# Output_curcuits_Page_3.net
KiCad netlist of a schematic drawn in Altium Designer
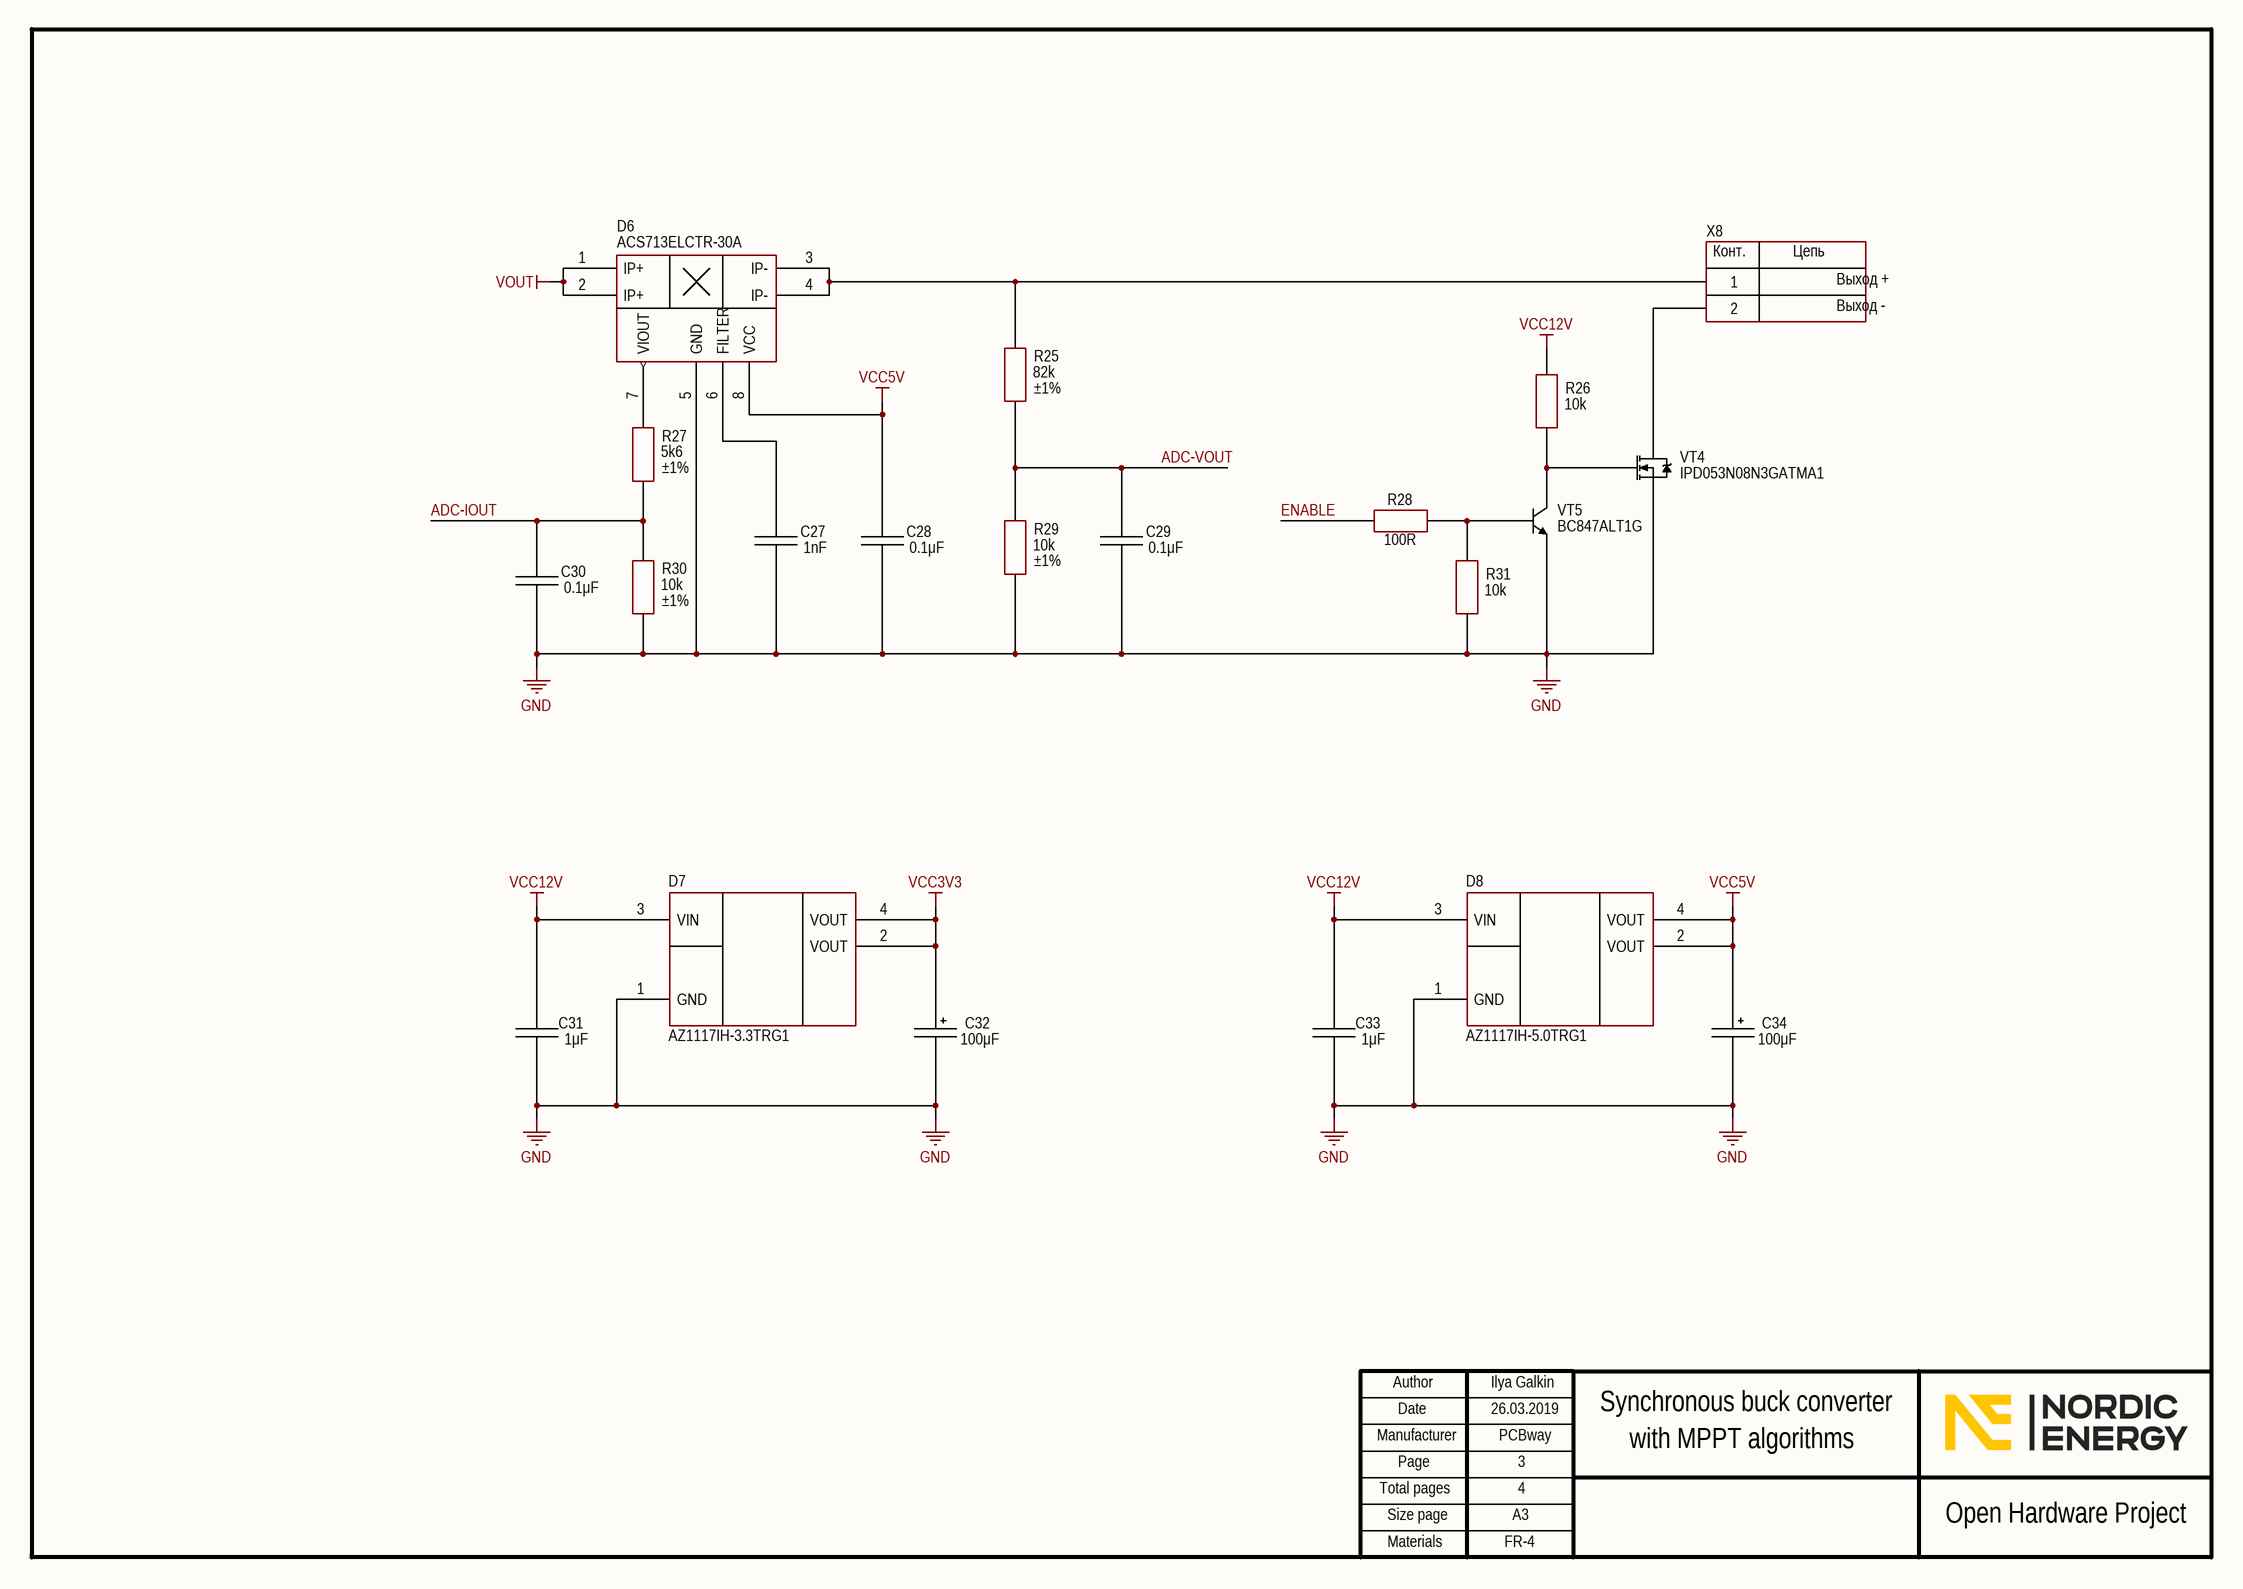
[diagram p0: Output curcuits. Page 3.SchDoc]

(export (version "E")
  (design (tool "Eeschema 10.0.6"))
  (components
    (comp (ref "C27")
      (value "1nF")
      (footprint "CH0805C")
      (fields (field (name "MANUFACTURER") "Yageo"))
      (libsource (lib "Discrete") (part "Capacitor"))
    )
    (comp (ref "C28")
      (value "0.1μF")
      (footprint "CH0805C")
      (fields (field (name "MANUFACTURER") "Yageo"))
      (libsource (lib "Discrete") (part "Capacitor"))
    )
    (comp (ref "C29")
      (value "0.1μF")
      (footprint "CH0805C")
      (fields (field (name "MANUFACTURER") "Yageo"))
      (libsource (lib "Discrete") (part "Capacitor"))
    )
    (comp (ref "C30")
      (value "0.1μF")
      (footprint "CH0805C")
      (fields (field (name "MANUFACTURER") "Yageo"))
      (libsource (lib "Discrete") (part "Capacitor"))
    )
    (comp (ref "C31")
      (value "1μF")
      (footprint "CH0805C")
      (fields (field (name "MANUFACTURER") "Yageo"))
      (libsource (lib "Discrete") (part "Capacitor"))
    )
    (comp (ref "C32")
      (value "100μF")
      (footprint "TANTAL_A")
      (fields (field (name "MANUFACTURER") "AVX"))
      (libsource (lib "Discrete") (part "TantalCap"))
    )
    (comp (ref "C33")
      (value "1μF")
      (footprint "CH0805C")
      (fields (field (name "MANUFACTURER") "Yageo"))
      (libsource (lib "Discrete") (part "Capacitor"))
    )
    (comp (ref "C34")
      (value "100μF")
      (footprint "TANTAL_A")
      (fields (field (name "MANUFACTURER") "AVX"))
      (libsource (lib "Discrete") (part "TantalCap"))
    )
    (comp (ref "D6")
      (value "ACS713ELCTR-30A")
      (footprint "8-SOIC")
      (description "Sensor")
      (fields (field (name "MANUFACTURER") "Allegro MicroSystems, LLC"))
      (libsource (lib "Power Supplies") (part "ACS713ELCTR-30A-T"))
    )
    (comp (ref "D7")
      (value "AZ1117IH-3.3TRG1")
      (footprint "SOT223")
      (description "LDO")
      (fields (field (name "MANUFACTURER") "Diodes Incorporated"))
      (libsource (lib "Power Supplies") (part "LDL1117S33R"))
    )
    (comp (ref "D8")
      (value "AZ1117IH-5.0TRG1")
      (footprint "SOT223")
      (description "LDO")
      (fields (field (name "MANUFACTURER") "Diodes Incorporated"))
      (libsource (lib "Power Supplies") (part "LDL1117S33R"))
    )
    (comp (ref "R25")
      (value "82k")
      (footprint "CH0805R")
      (fields (field (name "MANUFACTURER") "Yageo") (field (name "COMPONENTKIND") "±1%"))
      (libsource (lib "Discrete") (part "Resistor"))
    )
    (comp (ref "R26")
      (value "10k")
      (footprint "CH0805R")
      (fields (field (name "MANUFACTURER") "Yageo"))
      (libsource (lib "Discrete") (part "Resistor"))
    )
    (comp (ref "R27")
      (value "5k6")
      (footprint "CH0805R")
      (fields (field (name "MANUFACTURER") "Yageo") (field (name "COMPONENTKIND") "±1%"))
      (libsource (lib "Discrete") (part "Resistor"))
    )
    (comp (ref "R28")
      (value "100R")
      (footprint "CH0805R")
      (fields (field (name "MANUFACTURER") "Yageo"))
      (libsource (lib "") (part "Resistor_1"))
    )
    (comp (ref "R29")
      (value "10k")
      (footprint "CH0805R")
      (fields (field (name "MANUFACTURER") "Yageo") (field (name "COMPONENTKIND") "±1%"))
      (libsource (lib "Discrete") (part "Resistor"))
    )
    (comp (ref "R30")
      (value "10k")
      (footprint "CH0805R")
      (fields (field (name "MANUFACTURER") "Yageo") (field (name "COMPONENTKIND") "±1%"))
      (libsource (lib "Discrete") (part "Resistor"))
    )
    (comp (ref "R31")
      (value "10k")
      (footprint "CH0805R")
      (fields (field (name "MANUFACTURER") "Yageo"))
      (libsource (lib "Discrete") (part "Resistor"))
    )
    (comp (ref "VT4")
      (value "IPD053N08N3GATMA1")
      (footprint "D2PAK")
      (description "Mosfet")
      (fields (field (name "MANUFACTURER") "Infineon"))
      (libsource (lib "Transistor") (part "N-chanel"))
    )
    (comp (ref "VT5")
      (value "BC847ALT1G")
      (footprint "SOT23_123")
      (description "Bipolar")
      (fields (field (name "MANUFACTURER") "ON Semiconductor"))
      (libsource (lib "Transistor") (part "NPN"))
    )
    (comp (ref "X8")
      (value "6PCV-02-006")
      (footprint "CON: 6PCV-02-006")
      (fields (field (name "MANUFACTURER") "TE Connectivity"))
      (libsource (lib "Connectors") (part "2-Connector"))
    )
  )
  (nets
    (net (code "1") (name "/ADC-IOUT") (class "Default")
      (node (ref "C30") (pin "2") (pinfunction "2_2") (pintype "power_in"))
      (node (ref "R27") (pin "1") (pinfunction "1_1") (pintype "passive"))
      (node (ref "R30") (pin "2") (pinfunction "2_2") (pintype "passive"))
    )
    (net (code "2") (name "/ADC-VOUT") (class "Default")
      (node (ref "C29") (pin "2") (pinfunction "2_2") (pintype "power_in"))
      (node (ref "R25") (pin "1") (pinfunction "1_1") (pintype "passive"))
      (node (ref "R29") (pin "2") (pinfunction "2_2") (pintype "passive"))
    )
    (net (code "3") (name "/ENABLE") (class "Default")
      (node (ref "R28") (pin "1") (pinfunction "1_1") (pintype "passive"))
    )
    (net (code "4") (name "GND") (class "Default")
      (node (ref "C27") (pin "1") (pinfunction "1_1") (pintype "power_in"))
      (node (ref "C28") (pin "1") (pinfunction "1_1") (pintype "power_in"))
      (node (ref "C29") (pin "1") (pinfunction "1_1") (pintype "power_in"))
      (node (ref "C30") (pin "1") (pinfunction "1_1") (pintype "power_in"))
      (node (ref "C31") (pin "1") (pinfunction "1_1") (pintype "power_in"))
      (node (ref "C32") (pin "2") (pinfunction "2_2") (pintype "power_in"))
      (node (ref "C33") (pin "1") (pinfunction "1_1") (pintype "power_in"))
      (node (ref "C34") (pin "2") (pinfunction "2_2") (pintype "power_in"))
      (node (ref "D6") (pin "5") (pinfunction "GND_5") (pintype "passive"))
      (node (ref "D7") (pin "1") (pinfunction "GND_1") (pintype "power_in"))
      (node (ref "D8") (pin "1") (pinfunction "GND_1") (pintype "power_in"))
      (node (ref "R29") (pin "1") (pinfunction "1_1") (pintype "passive"))
      (node (ref "R30") (pin "1") (pinfunction "1_1") (pintype "passive"))
      (node (ref "R31") (pin "1") (pinfunction "1_1") (pintype "passive"))
      (node (ref "VT4") (pin "3") (pinfunction "S_3") (pintype "passive"))
      (node (ref "VT5") (pin "3") (pinfunction "E_3") (pintype "passive"))
    )
    (net (code "5") (name "Net-(D6-FILTER)") (class "Default")
      (node (ref "C27") (pin "2") (pinfunction "2_2") (pintype "power_in"))
      (node (ref "D6") (pin "6") (pinfunction "FILTER_6") (pintype "passive"))
    )
    (net (code "6") (name "Net-(D6-IP--Pad3)") (class "Default")
      (node (ref "D6") (pin "3") (pinfunction "IP-_3") (pintype "passive"))
      (node (ref "D6") (pin "4") (pinfunction "IP-_4") (pintype "passive"))
      (node (ref "R25") (pin "2") (pinfunction "2_2") (pintype "passive"))
      (node (ref "X8") (pin "1") (pinfunction "1_1") (pintype "passive"))
    )
    (net (code "7") (name "Net-(D6-VIOUT)") (class "Default")
      (node (ref "D6") (pin "7") (pinfunction "VIOUT_7") (pintype "output"))
      (node (ref "R27") (pin "2") (pinfunction "2_2") (pintype "passive"))
    )
    (net (code "8") (name "Net-(VT4-D)") (class "Default")
      (node (ref "VT4") (pin "2") (pinfunction "D_2") (pintype "passive"))
      (node (ref "X8") (pin "2") (pinfunction "2_2") (pintype "passive"))
    )
    (net (code "9") (name "Net-(VT4-G)") (class "Default")
      (node (ref "R26") (pin "1") (pinfunction "1_1") (pintype "passive"))
      (node (ref "VT4") (pin "1") (pinfunction "G_1") (pintype "passive"))
      (node (ref "VT5") (pin "2") (pinfunction "C_2") (pintype "passive"))
    )
    (net (code "10") (name "Net-(VT5-B)") (class "Default")
      (node (ref "R28") (pin "2") (pinfunction "2_2") (pintype "passive"))
      (node (ref "R31") (pin "2") (pinfunction "2_2") (pintype "passive"))
      (node (ref "VT5") (pin "1") (pinfunction "B_1") (pintype "passive"))
    )
    (net (code "11") (name "VCC3V3") (class "Default")
      (node (ref "C32") (pin "1") (pinfunction "1_1") (pintype "power_in"))
      (node (ref "D7") (pin "2") (pinfunction "VOUT_2") (pintype "power_in"))
      (node (ref "D7") (pin "4") (pinfunction "VOUT_4") (pintype "power_in"))
    )
    (net (code "12") (name "VCC5V") (class "Default")
      (node (ref "C28") (pin "2") (pinfunction "2_2") (pintype "power_in"))
      (node (ref "C34") (pin "1") (pinfunction "1_1") (pintype "power_in"))
      (node (ref "D6") (pin "8") (pinfunction "VCC_8") (pintype "passive"))
      (node (ref "D8") (pin "2") (pinfunction "VOUT_2") (pintype "power_in"))
      (node (ref "D8") (pin "4") (pinfunction "VOUT_4") (pintype "power_in"))
    )
    (net (code "13") (name "VCC12V") (class "Default")
      (node (ref "C31") (pin "2") (pinfunction "2_2") (pintype "power_in"))
      (node (ref "C33") (pin "2") (pinfunction "2_2") (pintype "power_in"))
      (node (ref "D7") (pin "3") (pinfunction "VIN_3") (pintype "power_in"))
      (node (ref "D8") (pin "3") (pinfunction "VIN_3") (pintype "power_in"))
      (node (ref "R26") (pin "2") (pinfunction "2_2") (pintype "passive"))
    )
    (net (code "14") (name "VOUT") (class "Default")
      (node (ref "D6") (pin "1") (pinfunction "IP+_1") (pintype "passive"))
      (node (ref "D6") (pin "2") (pinfunction "IP+_2") (pintype "passive"))
    )
  )
)
